# Sheet1.net
KiCad netlist of a schematic drawn in Altium Designer
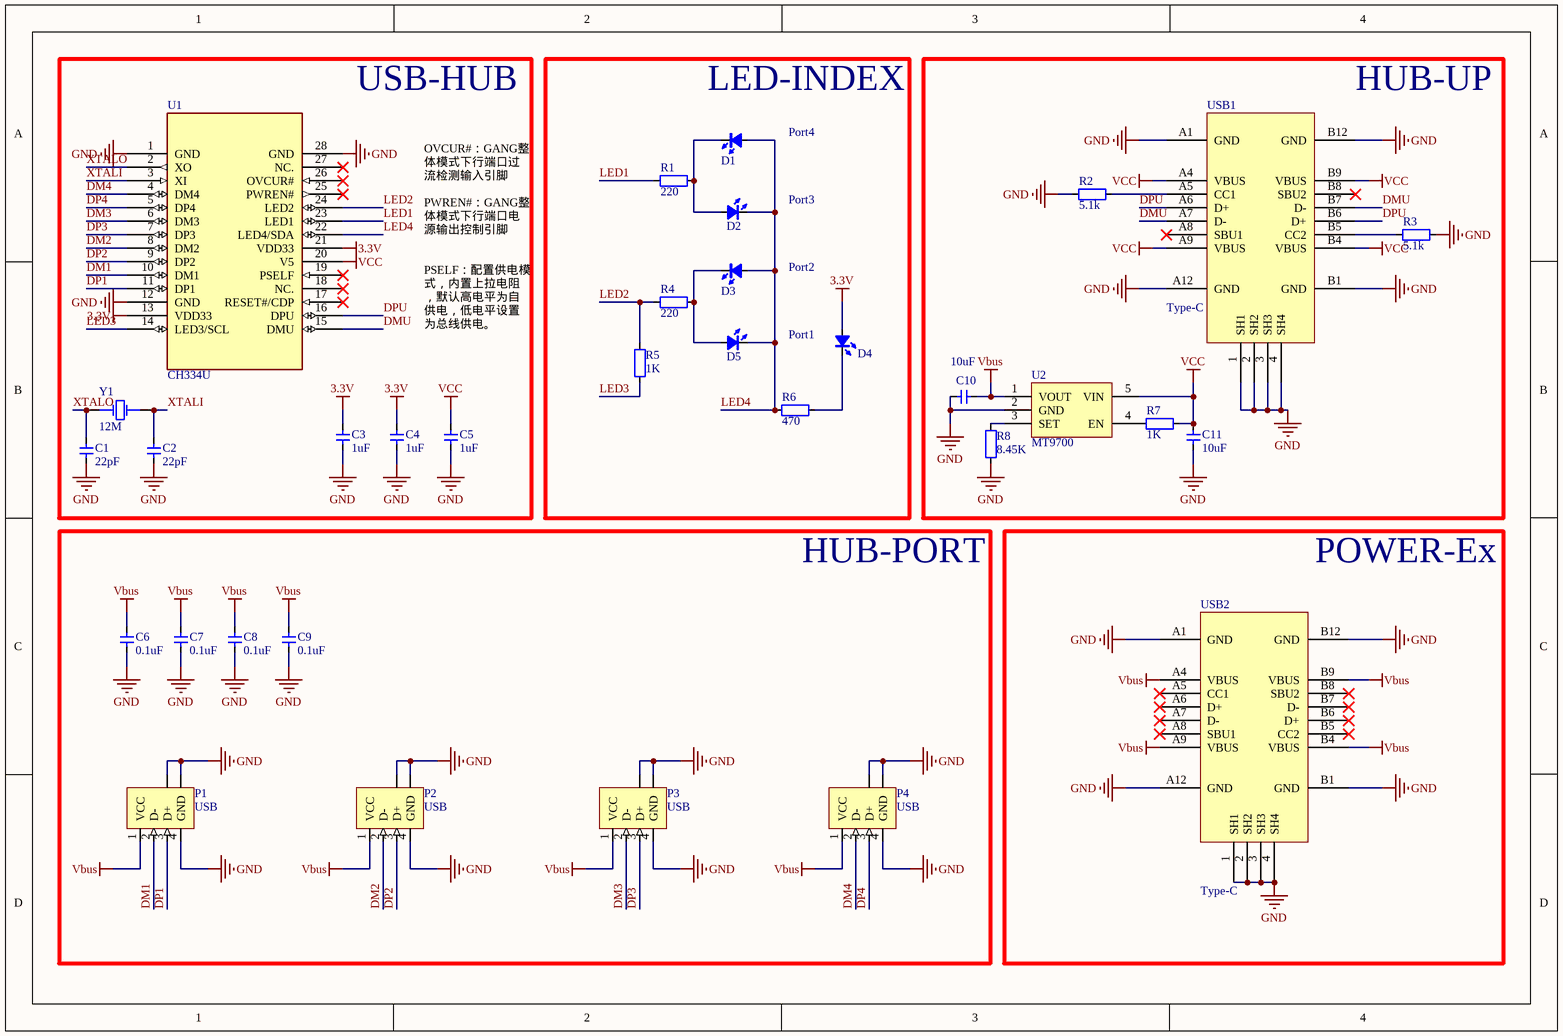
[diagram p0: Sheet1.SchDoc]

(export (version "E")
  (design (tool "Eeschema 10.0.6"))
  (components
    (comp (ref "C1")
      (value "22pF")
      (footprint "C0603")
      (description "Capacitor")
      (fields (field (name "PUBLISHER") "Altium Limited"))
      (libsource (lib "lycraft_lib") (part "贴片C"))
    )
    (comp (ref "C2")
      (value "22pF")
      (footprint "C0603")
      (description "Capacitor")
      (fields (field (name "PUBLISHER") "Altium Limited"))
      (libsource (lib "lycraft_lib") (part "贴片C"))
    )
    (comp (ref "C3")
      (value "1uF")
      (footprint "C0603")
      (description "Capacitor")
      (fields (field (name "PUBLISHER") "Altium Limited"))
      (libsource (lib "lycraft_lib") (part "贴片C"))
    )
    (comp (ref "C4")
      (value "1uF")
      (footprint "C0603")
      (description "Capacitor")
      (fields (field (name "PUBLISHER") "Altium Limited"))
      (libsource (lib "lycraft_lib") (part "贴片C"))
    )
    (comp (ref "C5")
      (value "1uF")
      (footprint "C0603")
      (description "Capacitor")
      (fields (field (name "PUBLISHER") "Altium Limited"))
      (libsource (lib "lycraft_lib") (part "贴片C"))
    )
    (comp (ref "C6")
      (value "0.1uF")
      (footprint "C0603")
      (description "Capacitor")
      (fields (field (name "PUBLISHER") "Altium Limited"))
      (libsource (lib "lycraft_lib") (part "贴片C"))
    )
    (comp (ref "C7")
      (value "0.1uF")
      (footprint "C0603")
      (description "Capacitor")
      (fields (field (name "PUBLISHER") "Altium Limited"))
      (libsource (lib "lycraft_lib") (part "贴片C"))
    )
    (comp (ref "C8")
      (value "0.1uF")
      (footprint "C0603")
      (description "Capacitor")
      (fields (field (name "PUBLISHER") "Altium Limited"))
      (libsource (lib "lycraft_lib") (part "贴片C"))
    )
    (comp (ref "C9")
      (value "0.1uF")
      (footprint "C0603")
      (description "Capacitor")
      (fields (field (name "PUBLISHER") "Altium Limited"))
      (libsource (lib "lycraft_lib") (part "贴片C"))
    )
    (comp (ref "C10")
      (value "10uF")
      (footprint "C0603")
      (description "Capacitor")
      (fields (field (name "PUBLISHER") "Altium Limited"))
      (libsource (lib "lycraft_lib") (part "贴片C"))
    )
    (comp (ref "C11")
      (value "10uF")
      (footprint "C0603")
      (description "Capacitor")
      (fields (field (name "PUBLISHER") "Altium Limited"))
      (libsource (lib "lycraft_lib") (part "贴片C"))
    )
    (comp (ref "D1")
      (value "color?")
      (footprint "LED0603")
      (description "LED")
      (libsource (lib "") (part "贴片LED_2"))
    )
    (comp (ref "D2")
      (value "color?")
      (footprint "LED0603")
      (description "LED")
      (libsource (lib "lycraft_lib") (part "贴片LED"))
    )
    (comp (ref "D3")
      (value "color?")
      (footprint "LED0603")
      (description "LED")
      (libsource (lib "") (part "贴片LED_2"))
    )
    (comp (ref "D4")
      (value "color?")
      (footprint "LED0603")
      (description "LED")
      (libsource (lib "") (part "贴片LED_1"))
    )
    (comp (ref "D5")
      (value "color?")
      (footprint "LED0603")
      (description "LED")
      (libsource (lib "lycraft_lib") (part "贴片LED"))
    )
    (comp (ref "P1")
      (value "USB")
      (footprint "USBB")
      (description "USB 1.1, Right Angle, SMT, A Type, Plug, 4 Position, Natural")
      (fields (field (name "PUBLISHER") "Altium Limited"))
      (libsource (lib "接插件") (part "USB"))
    )
    (comp (ref "P2")
      (value "USB")
      (footprint "USBB")
      (description "USB 1.1, Right Angle, SMT, A Type, Plug, 4 Position, Natural")
      (fields (field (name "PUBLISHER") "Altium Limited"))
      (libsource (lib "接插件") (part "USB"))
    )
    (comp (ref "P3")
      (value "USB")
      (footprint "USBB")
      (description "USB 1.1, Right Angle, SMT, A Type, Plug, 4 Position, Natural")
      (fields (field (name "PUBLISHER") "Altium Limited"))
      (libsource (lib "接插件") (part "USB"))
    )
    (comp (ref "P4")
      (value "USB")
      (footprint "USBB")
      (description "USB 1.1, Right Angle, SMT, A Type, Plug, 4 Position, Natural")
      (fields (field (name "PUBLISHER") "Altium Limited"))
      (libsource (lib "接插件") (part "USB"))
    )
    (comp (ref "R1")
      (value "220")
      (footprint "R0603")
      (description "Resistor")
      (fields (field (name "PUBLISHER") "Altium Limited"))
      (libsource (lib "lycraft_lib") (part "贴片R"))
    )
    (comp (ref "R2")
      (value "5.1k")
      (footprint "R0603")
      (description "Resistor")
      (fields (field (name "PUBLISHER") "Altium Limited"))
      (libsource (lib "lycraft_lib") (part "贴片R"))
    )
    (comp (ref "R3")
      (value "5.1k")
      (footprint "R0603")
      (description "Resistor")
      (fields (field (name "PUBLISHER") "Altium Limited"))
      (libsource (lib "lycraft_lib") (part "贴片R"))
    )
    (comp (ref "R4")
      (value "220")
      (footprint "R0603")
      (description "Resistor")
      (fields (field (name "PUBLISHER") "Altium Limited"))
      (libsource (lib "lycraft_lib") (part "贴片R"))
    )
    (comp (ref "R5")
      (value "1K")
      (footprint "R0603")
      (description "Resistor")
      (fields (field (name "PUBLISHER") "Altium Limited"))
      (libsource (lib "") (part "贴片R_1"))
    )
    (comp (ref "R6")
      (value "470")
      (footprint "R0603")
      (description "Resistor")
      (fields (field (name "PUBLISHER") "Altium Limited"))
      (libsource (lib "") (part "贴片R_2"))
    )
    (comp (ref "R7")
      (value "1K")
      (footprint "R0603")
      (description "Resistor")
      (fields (field (name "PUBLISHER") "Altium Limited"))
      (libsource (lib "lycraft_lib") (part "贴片R"))
    )
    (comp (ref "R8")
      (value "8.45K")
      (footprint "R0603")
      (description "Resistor")
      (fields (field (name "PUBLISHER") "Altium Limited"))
      (libsource (lib "") (part "贴片R_1"))
    )
    (comp (ref "U1")
      (value "CH334U")
      (footprint "QSOP28")
      (description "4 ports High-Speed USB MTT Hub with over current detect & power control")
      (libsource (lib "lycraft_lib") (part "CH334U"))
    )
    (comp (ref "U2")
      (value "MT9700")
      (footprint "SOT23-5")
      (description "USB电流保护")
      (libsource (lib "lycraft_lib") (part "MT9700"))
    )
    (comp (ref "USB1")
      (value "Type-C")
      (footprint "Type-C-TOP")
      (libsource (lib "接插件") (part "USB-Type-C-TOP"))
    )
    (comp (ref "USB2")
      (value "Type-C")
      (footprint "Type-C-TOP")
      (libsource (lib "接插件") (part "USB-Type-C-TOP"))
    )
    (comp (ref "Y1")
      (value "12M")
      (footprint "5032 2Pin")
      (libsource (lib "lycraft_lib") (part "XTAL 8Mhz 2pin"))
    )
  )
  (nets
    (net (code "1") (name "/DM1") (class "Default")
      (node (ref "P1") (pin "2") (pinfunction "D-_2") (pintype "input"))
      (node (ref "U1") (pin "10") (pinfunction "DM1_10") (pintype "bidirectional"))
    )
    (net (code "2") (name "/DM2") (class "Default")
      (node (ref "P2") (pin "2") (pinfunction "D-_2") (pintype "input"))
      (node (ref "U1") (pin "8") (pinfunction "DM2_8") (pintype "bidirectional"))
    )
    (net (code "3") (name "/DM3") (class "Default")
      (node (ref "P3") (pin "2") (pinfunction "D-_2") (pintype "input"))
      (node (ref "U1") (pin "6") (pinfunction "DM3_6") (pintype "bidirectional"))
    )
    (net (code "4") (name "/DM4") (class "Default")
      (node (ref "P4") (pin "2") (pinfunction "D-_2") (pintype "input"))
      (node (ref "U1") (pin "4") (pinfunction "DM4_4") (pintype "bidirectional"))
    )
    (net (code "5") (name "/DMU") (class "Default")
      (node (ref "U1") (pin "15") (pinfunction "DMU_15") (pintype "bidirectional"))
      (node (ref "USB1") (pin "A7") (pinfunction "D-_A7") (pintype "passive"))
      (node (ref "USB1") (pin "B7") (pinfunction "D-_B7") (pintype "passive"))
    )
    (net (code "6") (name "/DP1") (class "Default")
      (node (ref "P1") (pin "3") (pinfunction "D+_3") (pintype "input"))
      (node (ref "U1") (pin "11") (pinfunction "DP1_11") (pintype "bidirectional"))
    )
    (net (code "7") (name "/DP2") (class "Default")
      (node (ref "P2") (pin "3") (pinfunction "D+_3") (pintype "input"))
      (node (ref "U1") (pin "9") (pinfunction "DP2_9") (pintype "bidirectional"))
    )
    (net (code "8") (name "/DP3") (class "Default")
      (node (ref "P3") (pin "3") (pinfunction "D+_3") (pintype "input"))
      (node (ref "U1") (pin "7") (pinfunction "DP3_7") (pintype "bidirectional"))
    )
    (net (code "9") (name "/DP4") (class "Default")
      (node (ref "P4") (pin "3") (pinfunction "D+_3") (pintype "input"))
      (node (ref "U1") (pin "5") (pinfunction "DP4_5") (pintype "bidirectional"))
    )
    (net (code "10") (name "/DPU") (class "Default")
      (node (ref "U1") (pin "16") (pinfunction "DPU_16") (pintype "bidirectional"))
      (node (ref "USB1") (pin "A6") (pinfunction "D+_A6") (pintype "passive"))
      (node (ref "USB1") (pin "B6") (pinfunction "D+_B6") (pintype "passive"))
    )
    (net (code "11") (name "/LED1") (class "Default")
      (node (ref "R1") (pin "1") (pinfunction "1_1") (pintype "passive"))
      (node (ref "U1") (pin "23") (pinfunction "LED1_23") (pintype "bidirectional"))
    )
    (net (code "12") (name "/LED2") (class "Default")
      (node (ref "R4") (pin "1") (pinfunction "1_1") (pintype "passive"))
      (node (ref "R5") (pin "2") (pinfunction "2_2") (pintype "passive"))
      (node (ref "U1") (pin "24") (pinfunction "LED2_24") (pintype "bidirectional"))
    )
    (net (code "13") (name "/LED3") (class "Default")
      (node (ref "R5") (pin "1") (pinfunction "1_1") (pintype "passive"))
      (node (ref "U1") (pin "14") (pinfunction "LED3/SCL_14") (pintype "bidirectional"))
    )
    (net (code "14") (name "/LED4") (class "Default")
      (node (ref "D1") (pin "1") (pinfunction "A_1") (pintype "passive"))
      (node (ref "D2") (pin "2") (pinfunction "K_2") (pintype "passive"))
      (node (ref "D3") (pin "1") (pinfunction "A_1") (pintype "passive"))
      (node (ref "D5") (pin "2") (pinfunction "K_2") (pintype "passive"))
      (node (ref "R6") (pin "2") (pinfunction "2_2") (pintype "passive"))
      (node (ref "U1") (pin "22") (pinfunction "LED4/SDA_22") (pintype "bidirectional"))
    )
    (net (code "15") (name "/XTALI") (class "Default")
      (node (ref "C2") (pin "2") (pinfunction "2_2") (pintype "passive"))
      (node (ref "U1") (pin "3") (pinfunction "XI_3") (pintype "input"))
      (node (ref "Y1") (pin "2") (pinfunction "OSC2_2") (pintype "passive"))
    )
    (net (code "16") (name "/XTALO") (class "Default")
      (node (ref "C1") (pin "2") (pinfunction "2_2") (pintype "passive"))
      (node (ref "U1") (pin "2") (pinfunction "XO_2") (pintype "output"))
      (node (ref "Y1") (pin "1") (pinfunction "OSC1_1") (pintype "passive"))
    )
    (net (code "17") (name "3.3V") (class "Default")
      (node (ref "C3") (pin "2") (pinfunction "2_2") (pintype "passive"))
      (node (ref "C4") (pin "2") (pinfunction "2_2") (pintype "passive"))
      (node (ref "D4") (pin "1") (pinfunction "A_1") (pintype "passive"))
      (node (ref "U1") (pin "13") (pinfunction "VDD33_13") (pintype "power_in"))
      (node (ref "U1") (pin "21") (pinfunction "VDD33_21") (pintype "power_in"))
    )
    (net (code "18") (name "GND") (class "Default")
      (node (ref "C1") (pin "1") (pinfunction "1_1") (pintype "passive"))
      (node (ref "C10") (pin "2") (pinfunction "2_2") (pintype "passive"))
      (node (ref "C11") (pin "1") (pinfunction "1_1") (pintype "passive"))
      (node (ref "C2") (pin "1") (pinfunction "1_1") (pintype "passive"))
      (node (ref "C3") (pin "1") (pinfunction "1_1") (pintype "passive"))
      (node (ref "C4") (pin "1") (pinfunction "1_1") (pintype "passive"))
      (node (ref "C5") (pin "1") (pinfunction "1_1") (pintype "passive"))
      (node (ref "C6") (pin "1") (pinfunction "1_1") (pintype "passive"))
      (node (ref "C7") (pin "1") (pinfunction "1_1") (pintype "passive"))
      (node (ref "C8") (pin "1") (pinfunction "1_1") (pintype "passive"))
      (node (ref "C9") (pin "1") (pinfunction "1_1") (pintype "passive"))
      (node (ref "P1") (pin "4") (pinfunction "GND_4") (pintype "power_in"))
      (node (ref "P1") (pin "5") (pinfunction "SHLD_5") (pintype "passive"))
      (node (ref "P1") (pin "6") (pinfunction "SHLD_6") (pintype "passive"))
      (node (ref "P2") (pin "4") (pinfunction "GND_4") (pintype "power_in"))
      (node (ref "P2") (pin "5") (pinfunction "SHLD_5") (pintype "passive"))
      (node (ref "P2") (pin "6") (pinfunction "SHLD_6") (pintype "passive"))
      (node (ref "P3") (pin "4") (pinfunction "GND_4") (pintype "power_in"))
      (node (ref "P3") (pin "5") (pinfunction "SHLD_5") (pintype "passive"))
      (node (ref "P3") (pin "6") (pinfunction "SHLD_6") (pintype "passive"))
      (node (ref "P4") (pin "4") (pinfunction "GND_4") (pintype "power_in"))
      (node (ref "P4") (pin "5") (pinfunction "SHLD_5") (pintype "passive"))
      (node (ref "P4") (pin "6") (pinfunction "SHLD_6") (pintype "passive"))
      (node (ref "R2") (pin "1") (pinfunction "1_1") (pintype "passive"))
      (node (ref "R3") (pin "2") (pinfunction "2_2") (pintype "passive"))
      (node (ref "R8") (pin "1") (pinfunction "1_1") (pintype "passive"))
      (node (ref "U1") (pin "1") (pinfunction "GND_1") (pintype "power_in"))
      (node (ref "U1") (pin "12") (pinfunction "GND_12") (pintype "power_in"))
      (node (ref "U1") (pin "28") (pinfunction "GND_28") (pintype "power_in"))
      (node (ref "U2") (pin "2") (pinfunction "GND_2") (pintype "passive"))
      (node (ref "USB1") (pin "1") (pinfunction "SH1_1") (pintype "passive"))
      (node (ref "USB1") (pin "2") (pinfunction "SH2_2") (pintype "passive"))
      (node (ref "USB1") (pin "3") (pinfunction "SH3_3") (pintype "passive"))
      (node (ref "USB1") (pin "4") (pinfunction "SH4_4") (pintype "passive"))
      (node (ref "USB1") (pin "A1") (pinfunction "GND_A1") (pintype "passive"))
      (node (ref "USB1") (pin "A12") (pinfunction "GND_A12") (pintype "passive"))
      (node (ref "USB1") (pin "B1") (pinfunction "GND_B1") (pintype "passive"))
      (node (ref "USB1") (pin "B12") (pinfunction "GND_B12") (pintype "passive"))
      (node (ref "USB2") (pin "1") (pinfunction "SH1_1") (pintype "passive"))
      (node (ref "USB2") (pin "2") (pinfunction "SH2_2") (pintype "passive"))
      (node (ref "USB2") (pin "3") (pinfunction "SH3_3") (pintype "passive"))
      (node (ref "USB2") (pin "4") (pinfunction "SH4_4") (pintype "passive"))
      (node (ref "USB2") (pin "A1") (pinfunction "GND_A1") (pintype "passive"))
      (node (ref "USB2") (pin "A12") (pinfunction "GND_A12") (pintype "passive"))
      (node (ref "USB2") (pin "B1") (pinfunction "GND_B1") (pintype "passive"))
      (node (ref "USB2") (pin "B12") (pinfunction "GND_B12") (pintype "passive"))
    )
    (net (code "19") (name "Net-(D1-K)") (class "Default")
      (node (ref "D1") (pin "2") (pinfunction "K_2") (pintype "passive"))
      (node (ref "D2") (pin "1") (pinfunction "A_1") (pintype "passive"))
      (node (ref "R1") (pin "2") (pinfunction "2_2") (pintype "passive"))
    )
    (net (code "20") (name "Net-(D3-K)") (class "Default")
      (node (ref "D3") (pin "2") (pinfunction "K_2") (pintype "passive"))
      (node (ref "D5") (pin "1") (pinfunction "A_1") (pintype "passive"))
      (node (ref "R4") (pin "2") (pinfunction "2_2") (pintype "passive"))
    )
    (net (code "21") (name "Net-(D4-K)") (class "Default")
      (node (ref "D4") (pin "2") (pinfunction "K_2") (pintype "passive"))
      (node (ref "R6") (pin "1") (pinfunction "1_1") (pintype "passive"))
    )
    (net (code "22") (name "Net-(U2-EN)") (class "Default")
      (node (ref "R7") (pin "1") (pinfunction "1_1") (pintype "passive"))
      (node (ref "U2") (pin "4") (pinfunction "EN_4") (pintype "passive"))
    )
    (net (code "23") (name "Net-(U2-SET)") (class "Default")
      (node (ref "R8") (pin "2") (pinfunction "2_2") (pintype "passive"))
      (node (ref "U2") (pin "3") (pinfunction "SET_3") (pintype "passive"))
    )
    (net (code "24") (name "Net-(USB1-CC1)") (class "Default")
      (node (ref "R2") (pin "2") (pinfunction "2_2") (pintype "passive"))
      (node (ref "USB1") (pin "A5") (pinfunction "CC1_A5") (pintype "passive"))
    )
    (net (code "25") (name "Net-(USB1-CC2)") (class "Default")
      (node (ref "R3") (pin "1") (pinfunction "1_1") (pintype "passive"))
      (node (ref "USB1") (pin "B5") (pinfunction "CC2_B5") (pintype "passive"))
    )
    (net (code "26") (name "VCC") (class "Default")
      (node (ref "C11") (pin "2") (pinfunction "2_2") (pintype "passive"))
      (node (ref "C5") (pin "2") (pinfunction "2_2") (pintype "passive"))
      (node (ref "R7") (pin "2") (pinfunction "2_2") (pintype "passive"))
      (node (ref "U1") (pin "20") (pinfunction "V5_20") (pintype "power_in"))
      (node (ref "U2") (pin "5") (pinfunction "VIN_5") (pintype "passive"))
      (node (ref "USB1") (pin "A4") (pinfunction "VBUS_A4") (pintype "passive"))
      (node (ref "USB1") (pin "A9") (pinfunction "VBUS_A9") (pintype "passive"))
      (node (ref "USB1") (pin "B4") (pinfunction "VBUS_B4") (pintype "passive"))
      (node (ref "USB1") (pin "B9") (pinfunction "VBUS_B9") (pintype "passive"))
    )
    (net (code "27") (name "Vbus") (class "Default")
      (node (ref "C10") (pin "1") (pinfunction "1_1") (pintype "passive"))
      (node (ref "C6") (pin "2") (pinfunction "2_2") (pintype "passive"))
      (node (ref "C7") (pin "2") (pinfunction "2_2") (pintype "passive"))
      (node (ref "C8") (pin "2") (pinfunction "2_2") (pintype "passive"))
      (node (ref "C9") (pin "2") (pinfunction "2_2") (pintype "passive"))
      (node (ref "P1") (pin "1") (pinfunction "VCC_1") (pintype "power_in"))
      (node (ref "P2") (pin "1") (pinfunction "VCC_1") (pintype "power_in"))
      (node (ref "P3") (pin "1") (pinfunction "VCC_1") (pintype "power_in"))
      (node (ref "P4") (pin "1") (pinfunction "VCC_1") (pintype "power_in"))
      (node (ref "U2") (pin "1") (pinfunction "VOUT_1") (pintype "passive"))
      (node (ref "USB2") (pin "A4") (pinfunction "VBUS_A4") (pintype "passive"))
      (node (ref "USB2") (pin "A9") (pinfunction "VBUS_A9") (pintype "passive"))
      (node (ref "USB2") (pin "B4") (pinfunction "VBUS_B4") (pintype "passive"))
      (node (ref "USB2") (pin "B9") (pinfunction "VBUS_B9") (pintype "passive"))
    )
    (net (code "28") (name "unconnected-(U1-NC.-Pad18)") (class "Default")
      (node (ref "U1") (pin "18") (pinfunction "NC._18") (pintype "passive+no_connect"))
    )
    (net (code "29") (name "unconnected-(U1-NC.-Pad27)") (class "Default")
      (node (ref "U1") (pin "27") (pinfunction "NC._27") (pintype "passive+no_connect"))
    )
    (net (code "30") (name "unconnected-(U1-OVCUR#-Pad26)") (class "Default")
      (node (ref "U1") (pin "26") (pinfunction "OVCUR#_26") (pintype "input+no_connect"))
    )
    (net (code "31") (name "unconnected-(U1-PSELF-Pad19)") (class "Default")
      (node (ref "U1") (pin "19") (pinfunction "PSELF_19") (pintype "input+no_connect"))
    )
    (net (code "32") (name "unconnected-(U1-PWREN#-Pad25)") (class "Default")
      (node (ref "U1") (pin "25") (pinfunction "PWREN#_25") (pintype "output+no_connect"))
    )
    (net (code "33") (name "unconnected-(U1-RESET#{slash}CDP-Pad17)") (class "Default")
      (node (ref "U1") (pin "17") (pinfunction "RESET#/CDP_17") (pintype "input+no_connect"))
    )
    (net (code "34") (name "unconnected-(USB1-SBU1-PadA8)") (class "Default")
      (node (ref "USB1") (pin "A8") (pinfunction "SBU1_A8") (pintype "passive+no_connect"))
    )
    (net (code "35") (name "unconnected-(USB1-SBU2-PadB8)") (class "Default")
      (node (ref "USB1") (pin "B8") (pinfunction "SBU2_B8") (pintype "passive+no_connect"))
    )
    (net (code "36") (name "unconnected-(USB2-CC1-PadA5)") (class "Default")
      (node (ref "USB2") (pin "A5") (pinfunction "CC1_A5") (pintype "passive+no_connect"))
    )
    (net (code "37") (name "unconnected-(USB2-CC2-PadB5)") (class "Default")
      (node (ref "USB2") (pin "B5") (pinfunction "CC2_B5") (pintype "passive+no_connect"))
    )
    (net (code "38") (name "unconnected-(USB2-D+-PadA6)") (class "Default")
      (node (ref "USB2") (pin "A6") (pinfunction "D+_A6") (pintype "passive+no_connect"))
    )
    (net (code "39") (name "unconnected-(USB2-D+-PadB6)") (class "Default")
      (node (ref "USB2") (pin "B6") (pinfunction "D+_B6") (pintype "passive+no_connect"))
    )
    (net (code "40") (name "unconnected-(USB2-D--PadA7)") (class "Default")
      (node (ref "USB2") (pin "A7") (pinfunction "D-_A7") (pintype "passive+no_connect"))
    )
    (net (code "41") (name "unconnected-(USB2-D--PadB7)") (class "Default")
      (node (ref "USB2") (pin "B7") (pinfunction "D-_B7") (pintype "passive+no_connect"))
    )
    (net (code "42") (name "unconnected-(USB2-SBU1-PadA8)") (class "Default")
      (node (ref "USB2") (pin "A8") (pinfunction "SBU1_A8") (pintype "passive+no_connect"))
    )
    (net (code "43") (name "unconnected-(USB2-SBU2-PadB8)") (class "Default")
      (node (ref "USB2") (pin "B8") (pinfunction "SBU2_B8") (pintype "passive+no_connect"))
    )
  )
)
